# display_adapter_v3_docFile.net
KiCad netlist of a schematic drawn in EasyEDA Pro
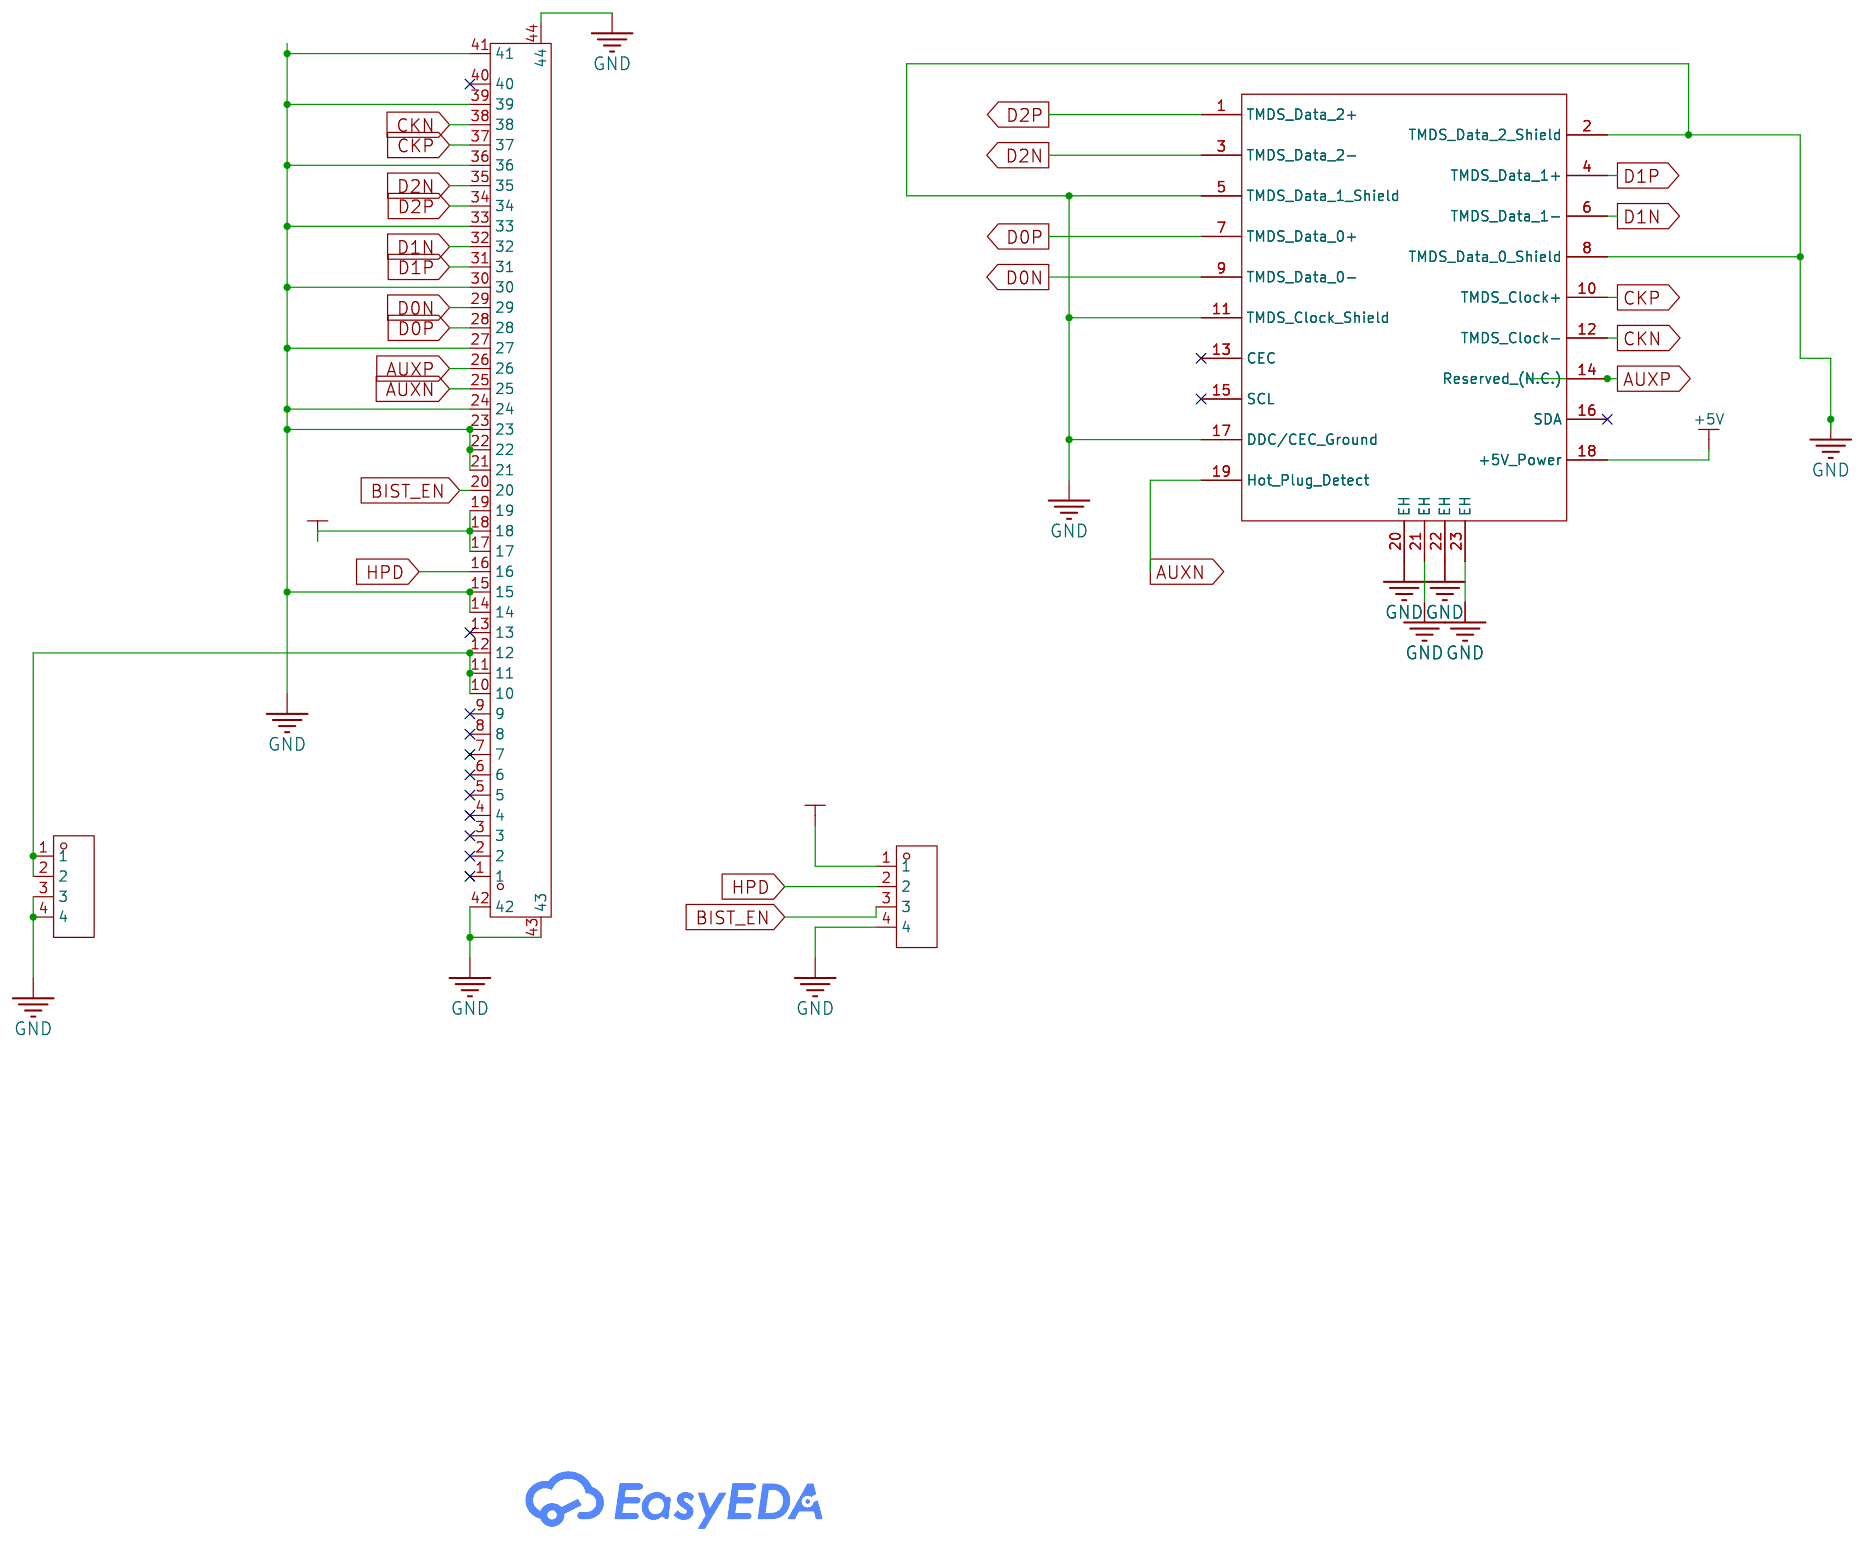
[diagram p0: schematic sheet]

(export (version "E")
  (design (tool "Eeschema 10.0.6"))
  (components
    (comp (ref "CN1")
      (value "20455-040E-76")
      (footprint "easyedapro:CONN-SMD_40P-P-0.50_20455-040E-76")
      (fields (field (name "Manufacturer") "I-PEX(第一精工)"))
      (libsource (lib "easyedapro") (part "20455-040E-76"))
    )
    (comp (ref "CN2")
      (value "HYC109-HDMIA19-160")
      (footprint "easyedapro:HDMI-SMD_HYC109-HDMIA19-160")
      (fields (field (name "Manufacturer") "华宇创"))
      (libsource (lib "easyedapro") (part "HYC109-HDMIA19-160"))
    )
    (comp (ref "H1")
      (value "PZ254V-11-04P")
      (footprint "easyedapro:HDR-TH_4P-P2.54-V-M")
      (fields (field (name "Manufacturer") "XFCN(兴飞)"))
      (libsource (lib "easyedapro") (part "PZ254V-11-04P_C2691448"))
    )
    (comp (ref "H2")
      (value "PZ254V-11-04P")
      (footprint "easyedapro:HDR-TH_4P-P2.54-V-M")
      (fields (field (name "Manufacturer") "XFCN(兴飞)"))
      (libsource (lib "easyedapro") (part "PZ254V-11-04P_C2691448"))
    )
  )
  (nets
    (net (code "1") (name "+3.3V") (class "Default")
      (node (ref "CN1") (pin "17") (pinfunction "17_17") (pintype "unspecified"))
      (node (ref "CN1") (pin "18") (pinfunction "18_18") (pintype "unspecified"))
      (node (ref "CN1") (pin "19") (pinfunction "19_19") (pintype "unspecified"))
      (node (ref "H2") (pin "1") (pinfunction "1_1") (pintype "input"))
    )
    (net (code "2") (name "+5V") (class "Default")
      (node (ref "CN2") (pin "18") (pinfunction "+5V_Power_18") (pintype "unspecified"))
    )
    (net (code "3") (name "AUXN") (class "Default")
      (node (ref "CN1") (pin "25") (pinfunction "25_25") (pintype "unspecified"))
      (node (ref "CN2") (pin "19") (pinfunction "Hot_Plug_Detect_19") (pintype "unspecified"))
    )
    (net (code "4") (name "AUXP") (class "Default")
      (node (ref "CN1") (pin "26") (pinfunction "26_26") (pintype "unspecified"))
      (node (ref "CN2") (pin "14") (pinfunction "Reserved_(N.C.)_14") (pintype "unspecified"))
    )
    (net (code "5") (name "BIST_EN") (class "Default")
      (node (ref "CN1") (pin "20") (pinfunction "20_20") (pintype "unspecified"))
      (node (ref "H2") (pin "3") (pinfunction "3_3") (pintype "input"))
    )
    (net (code "6") (name "CKN") (class "Default")
      (node (ref "CN1") (pin "38") (pinfunction "38_38") (pintype "unspecified"))
      (node (ref "CN2") (pin "12") (pinfunction "TMDS_Clock-_12") (pintype "unspecified"))
    )
    (net (code "7") (name "CKP") (class "Default")
      (node (ref "CN1") (pin "37") (pinfunction "37_37") (pintype "unspecified"))
      (node (ref "CN2") (pin "10") (pinfunction "TMDS_Clock+_10") (pintype "unspecified"))
    )
    (net (code "8") (name "D0N") (class "Default")
      (node (ref "CN1") (pin "29") (pinfunction "29_29") (pintype "unspecified"))
      (node (ref "CN2") (pin "9") (pinfunction "TMDS_Data_0-_9") (pintype "unspecified"))
    )
    (net (code "9") (name "D0P") (class "Default")
      (node (ref "CN1") (pin "28") (pinfunction "28_28") (pintype "unspecified"))
      (node (ref "CN2") (pin "7") (pinfunction "TMDS_Data_0+_7") (pintype "unspecified"))
    )
    (net (code "10") (name "D1N") (class "Default")
      (node (ref "CN1") (pin "32") (pinfunction "32_32") (pintype "unspecified"))
      (node (ref "CN2") (pin "6") (pinfunction "TMDS_Data_1-_6") (pintype "unspecified"))
    )
    (net (code "11") (name "D1P") (class "Default")
      (node (ref "CN1") (pin "31") (pinfunction "31_31") (pintype "unspecified"))
      (node (ref "CN2") (pin "4") (pinfunction "TMDS_Data_1+_4") (pintype "unspecified"))
    )
    (net (code "12") (name "D2N") (class "Default")
      (node (ref "CN1") (pin "35") (pinfunction "35_35") (pintype "unspecified"))
      (node (ref "CN2") (pin "3") (pinfunction "TMDS_Data_2-_3") (pintype "unspecified"))
    )
    (net (code "13") (name "D2P") (class "Default")
      (node (ref "CN1") (pin "34") (pinfunction "34_34") (pintype "unspecified"))
      (node (ref "CN2") (pin "1") (pinfunction "TMDS_Data_2+_1") (pintype "unspecified"))
    )
    (net (code "14") (name "GND") (class "Default")
      (node (ref "CN1") (pin "14") (pinfunction "14_14") (pintype "unspecified"))
      (node (ref "CN1") (pin "15") (pinfunction "15_15") (pintype "unspecified"))
      (node (ref "CN1") (pin "21") (pinfunction "21_21") (pintype "unspecified"))
      (node (ref "CN1") (pin "22") (pinfunction "22_22") (pintype "unspecified"))
      (node (ref "CN1") (pin "23") (pinfunction "23_23") (pintype "unspecified"))
      (node (ref "CN1") (pin "24") (pinfunction "24_24") (pintype "unspecified"))
      (node (ref "CN1") (pin "27") (pinfunction "27_27") (pintype "unspecified"))
      (node (ref "CN1") (pin "30") (pinfunction "30_30") (pintype "unspecified"))
      (node (ref "CN1") (pin "33") (pinfunction "33_33") (pintype "unspecified"))
      (node (ref "CN1") (pin "36") (pinfunction "36_36") (pintype "unspecified"))
      (node (ref "CN1") (pin "39") (pinfunction "39_39") (pintype "unspecified"))
      (node (ref "CN1") (pin "41") (pinfunction "41_41") (pintype "unspecified"))
      (node (ref "CN1") (pin "42") (pinfunction "42_42") (pintype "unspecified"))
      (node (ref "CN1") (pin "43") (pinfunction "43_43") (pintype "unspecified"))
      (node (ref "CN1") (pin "44") (pinfunction "44_44") (pintype "unspecified"))
      (node (ref "CN2") (pin "11") (pinfunction "TMDS_Clock_Shield_11") (pintype "unspecified"))
      (node (ref "CN2") (pin "17") (pinfunction "DDC/CEC_Ground_17") (pintype "unspecified"))
      (node (ref "CN2") (pin "2") (pinfunction "TMDS_Data_2_Shield_2") (pintype "unspecified"))
      (node (ref "CN2") (pin "20") (pinfunction "EH_20") (pintype "unspecified"))
      (node (ref "CN2") (pin "21") (pinfunction "EH_21") (pintype "unspecified"))
      (node (ref "CN2") (pin "22") (pinfunction "EH_22") (pintype "unspecified"))
      (node (ref "CN2") (pin "23") (pinfunction "EH_23") (pintype "unspecified"))
      (node (ref "CN2") (pin "5") (pinfunction "TMDS_Data_1_Shield_5") (pintype "unspecified"))
      (node (ref "CN2") (pin "8") (pinfunction "TMDS_Data_0_Shield_8") (pintype "unspecified"))
      (node (ref "H1") (pin "3") (pinfunction "3_3") (pintype "input"))
      (node (ref "H1") (pin "4") (pinfunction "4_4") (pintype "input"))
      (node (ref "H2") (pin "4") (pinfunction "4_4") (pintype "input"))
    )
    (net (code "15") (name "HPD") (class "Default")
      (node (ref "CN1") (pin "16") (pinfunction "16_16") (pintype "unspecified"))
      (node (ref "H2") (pin "2") (pinfunction "2_2") (pintype "input"))
    )
    (net (code "16") (name "Net-(CN1-Pad10)") (class "Default")
      (node (ref "CN1") (pin "10") (pinfunction "10_10") (pintype "unspecified"))
      (node (ref "CN1") (pin "11") (pinfunction "11_11") (pintype "unspecified"))
      (node (ref "CN1") (pin "12") (pinfunction "12_12") (pintype "unspecified"))
      (node (ref "H1") (pin "1") (pinfunction "1_1") (pintype "input"))
      (node (ref "H1") (pin "2") (pinfunction "2_2") (pintype "input"))
    )
    (net (code "17") (name "unconnected-(CN1-Pad1)") (class "Default")
      (node (ref "CN1") (pin "1") (pinfunction "1_1") (pintype "unspecified+no_connect"))
    )
    (net (code "18") (name "unconnected-(CN1-Pad2)") (class "Default")
      (node (ref "CN1") (pin "2") (pinfunction "2_2") (pintype "unspecified+no_connect"))
    )
    (net (code "19") (name "unconnected-(CN1-Pad3)") (class "Default")
      (node (ref "CN1") (pin "3") (pinfunction "3_3") (pintype "unspecified+no_connect"))
    )
    (net (code "20") (name "unconnected-(CN1-Pad4)") (class "Default")
      (node (ref "CN1") (pin "4") (pinfunction "4_4") (pintype "unspecified+no_connect"))
    )
    (net (code "21") (name "unconnected-(CN1-Pad5)") (class "Default")
      (node (ref "CN1") (pin "5") (pinfunction "5_5") (pintype "unspecified+no_connect"))
    )
    (net (code "22") (name "unconnected-(CN1-Pad6)") (class "Default")
      (node (ref "CN1") (pin "6") (pinfunction "6_6") (pintype "unspecified+no_connect"))
    )
    (net (code "23") (name "unconnected-(CN1-Pad7)") (class "Default")
      (node (ref "CN1") (pin "7") (pinfunction "7_7") (pintype "unspecified+no_connect"))
    )
    (net (code "24") (name "unconnected-(CN1-Pad8)") (class "Default")
      (node (ref "CN1") (pin "8") (pinfunction "8_8") (pintype "unspecified+no_connect"))
    )
    (net (code "25") (name "unconnected-(CN1-Pad9)") (class "Default")
      (node (ref "CN1") (pin "9") (pinfunction "9_9") (pintype "unspecified+no_connect"))
    )
    (net (code "26") (name "unconnected-(CN1-Pad13)") (class "Default")
      (node (ref "CN1") (pin "13") (pinfunction "13_13") (pintype "unspecified+no_connect"))
    )
    (net (code "27") (name "unconnected-(CN1-Pad40)") (class "Default")
      (node (ref "CN1") (pin "40") (pinfunction "40_40") (pintype "unspecified+no_connect"))
    )
    (net (code "28") (name "unconnected-(CN2-CEC-Pad13)") (class "Default")
      (node (ref "CN2") (pin "13") (pinfunction "CEC_13") (pintype "unspecified+no_connect"))
    )
    (net (code "29") (name "unconnected-(CN2-SCL-Pad15)") (class "Default")
      (node (ref "CN2") (pin "15") (pinfunction "SCL_15") (pintype "unspecified+no_connect"))
    )
    (net (code "30") (name "unconnected-(CN2-SDA-Pad16)") (class "Default")
      (node (ref "CN2") (pin "16") (pinfunction "SDA_16") (pintype "unspecified+no_connect"))
    )
  )
)
